# PWM_Connector.net
KiCad netlist of a schematic drawn in EAGLE
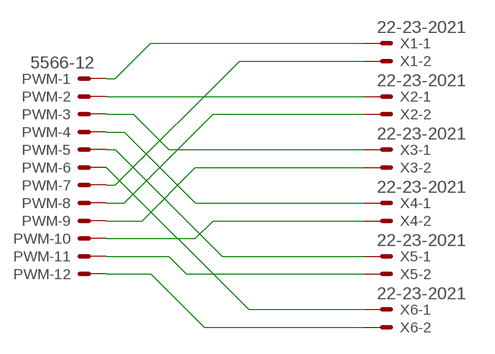
[diagram p0: schematic, sheet 1]

(export (version "E")
  (design (tool "Eeschema 10.0.6"))
  (components
    (comp (ref "PWM")
      (value "5566-12")
      (footprint "eagle-import:5566-12")
      (libsource (lib "eagle-import") (part "5566-12"))
    )
    (comp (ref "X1")
      (value "22-23-2021")
      (footprint "eagle-import:22-23-2021")
      (fields (field (name "MF") "MOLEX"))
      (libsource (lib "eagle-import") (part "22-23-2021"))
    )
    (comp (ref "X2")
      (value "22-23-2021")
      (footprint "eagle-import:22-23-2021")
      (fields (field (name "MF") "MOLEX"))
      (libsource (lib "eagle-import") (part "22-23-2021"))
    )
    (comp (ref "X3")
      (value "22-23-2021")
      (footprint "eagle-import:22-23-2021")
      (fields (field (name "MF") "MOLEX"))
      (libsource (lib "eagle-import") (part "22-23-2021"))
    )
    (comp (ref "X4")
      (value "22-23-2021")
      (footprint "eagle-import:22-23-2021")
      (fields (field (name "MF") "MOLEX"))
      (libsource (lib "eagle-import") (part "22-23-2021"))
    )
    (comp (ref "X5")
      (value "22-23-2021")
      (footprint "eagle-import:22-23-2021")
      (fields (field (name "MF") "MOLEX"))
      (libsource (lib "eagle-import") (part "22-23-2021"))
    )
    (comp (ref "X6")
      (value "22-23-2021")
      (footprint "eagle-import:22-23-2021")
      (fields (field (name "MF") "MOLEX"))
      (libsource (lib "eagle-import") (part "22-23-2021"))
    )
  )
  (nets
    (net (code "1") (name "Net-(PWMA-S)") (class "Default")
      (node (ref "PWM") (pin "1") (pinfunction "S_1") (pintype "passive"))
      (node (ref "X1") (pin "1") (pinfunction "S_1") (pintype "passive"))
    )
    (net (code "2") (name "Net-(PWMB-S)") (class "Default")
      (node (ref "PWM") (pin "10") (pinfunction "S_10") (pintype "passive"))
      (node (ref "X4") (pin "2") (pinfunction "S_2") (pintype "passive"))
    )
    (net (code "3") (name "Net-(PWMC-S)") (class "Default")
      (node (ref "PWM") (pin "11") (pinfunction "S_11") (pintype "passive"))
      (node (ref "X5") (pin "2") (pinfunction "S_2") (pintype "passive"))
    )
    (net (code "4") (name "Net-(PWMD-S)") (class "Default")
      (node (ref "PWM") (pin "12") (pinfunction "S_12") (pintype "passive"))
      (node (ref "X6") (pin "2") (pinfunction "S_2") (pintype "passive"))
    )
    (net (code "5") (name "Net-(PWME-S)") (class "Default")
      (node (ref "PWM") (pin "2") (pinfunction "S_2") (pintype "passive"))
      (node (ref "X2") (pin "1") (pinfunction "S_1") (pintype "passive"))
    )
    (net (code "6") (name "Net-(PWMF-S)") (class "Default")
      (node (ref "PWM") (pin "3") (pinfunction "S_3") (pintype "passive"))
      (node (ref "X3") (pin "1") (pinfunction "S_1") (pintype "passive"))
    )
    (net (code "7") (name "Net-(PWMG-S)") (class "Default")
      (node (ref "PWM") (pin "4") (pinfunction "S_4") (pintype "passive"))
      (node (ref "X4") (pin "1") (pinfunction "S_1") (pintype "passive"))
    )
    (net (code "8") (name "Net-(PWMH-S)") (class "Default")
      (node (ref "PWM") (pin "5") (pinfunction "S_5") (pintype "passive"))
      (node (ref "X5") (pin "1") (pinfunction "S_1") (pintype "passive"))
    )
    (net (code "9") (name "Net-(PWMI-S)") (class "Default")
      (node (ref "PWM") (pin "6") (pinfunction "S_6") (pintype "passive"))
      (node (ref "X6") (pin "1") (pinfunction "S_1") (pintype "passive"))
    )
    (net (code "10") (name "Net-(PWMJ-S)") (class "Default")
      (node (ref "PWM") (pin "7") (pinfunction "S_7") (pintype "passive"))
      (node (ref "X1") (pin "2") (pinfunction "S_2") (pintype "passive"))
    )
    (net (code "11") (name "Net-(PWMK-S)") (class "Default")
      (node (ref "PWM") (pin "8") (pinfunction "S_8") (pintype "passive"))
      (node (ref "X2") (pin "2") (pinfunction "S_2") (pintype "passive"))
    )
    (net (code "12") (name "Net-(PWML-S)") (class "Default")
      (node (ref "PWM") (pin "9") (pinfunction "S_9") (pintype "passive"))
      (node (ref "X3") (pin "2") (pinfunction "S_2") (pintype "passive"))
    )
  )
)
